# daughter-double3.net
KiCad netlist of a schematic drawn in EAGLE
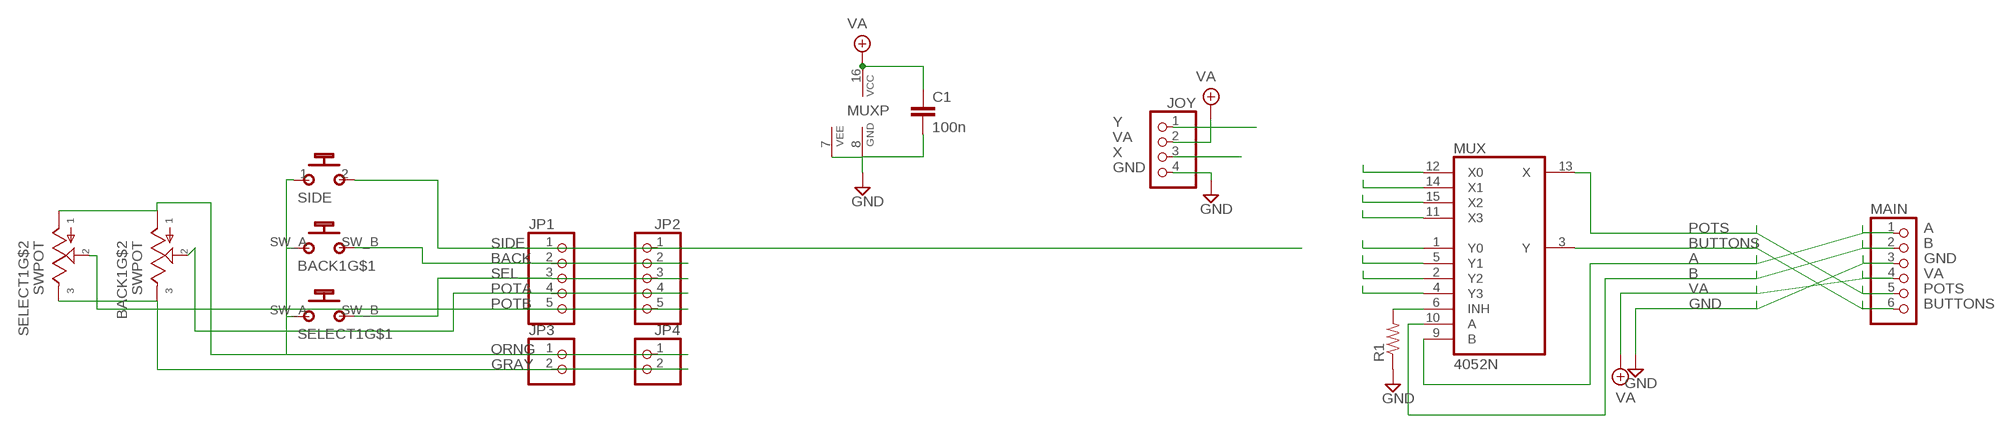
[diagram p0: schematic, sheet 1]

(export (version "E")
  (design (tool "Eeschema 10.0.6"))
  (components
    (comp (ref "BACK1")
      (value "SWPOT")
      (footprint "eagle-import:SWPOT")
      (libsource (lib "eagle-import") (part "SWPOT"))
    )
    (comp (ref "C1")
      (value "100n")
      (footprint "eagle-import:050X030_050_3")
      (libsource (lib "eagle-import") (part "050X030_050"))
    )
    (comp (ref "JOY")
      (value "PINHD-1X4")
      (footprint "eagle-import:1X04")
      (libsource (lib "eagle-import") (part "PINHD-1X4"))
    )
    (comp (ref "JP1")
      (value "PINHD-1X5")
      (footprint "eagle-import:1X05")
      (libsource (lib "eagle-import") (part "PINHD-1X5"))
    )
    (comp (ref "JP2")
      (value "PINHD-1X5")
      (footprint "eagle-import:1X05")
      (libsource (lib "eagle-import") (part "PINHD-1X5"))
    )
    (comp (ref "JP3")
      (value "PINHD-1X2")
      (footprint "eagle-import:1X02")
      (libsource (lib "eagle-import") (part "PINHD-1X2"))
    )
    (comp (ref "JP4")
      (value "PINHD-1X2")
      (footprint "eagle-import:1X02")
      (libsource (lib "eagle-import") (part "PINHD-1X2"))
    )
    (comp (ref "MAIN")
      (value "PINHD-1X6")
      (footprint "eagle-import:1X06")
      (libsource (lib "eagle-import") (part "PINHD-1X6"))
    )
    (comp (ref "MUX")
      (value "4052N")
      (footprint "eagle-import:DIL16")
      (libsource (lib "eagle-import") (part "4052N"))
    )
    (comp (ref "R1")
      (value "6MM.1")
      (footprint "eagle-import:R0207_1V")
      (libsource (lib "eagle-import") (part "6MM.1"))
    )
    (comp (ref "SELECT1")
      (value "SWPOT")
      (footprint "eagle-import:SWPOT")
      (libsource (lib "eagle-import") (part "SWPOT"))
    )
    (comp (ref "SIDE")
      (value "MOMENTARYSPST1")
      (footprint "eagle-import:SPST")
      (libsource (lib "eagle-import") (part "MOMENTARYSPST1"))
    )
  )
  (nets
    (net (code "1") (name "/A") (class "Default")
      (node (ref "MAIN") (pin "1") (pinfunction "1_1") (pintype "passive"))
      (node (ref "MUX") (pin "9") (pinfunction "B_9") (pintype "input"))
    )
    (net (code "2") (name "/B") (class "Default")
      (node (ref "MAIN") (pin "2") (pinfunction "2_2") (pintype "passive"))
      (node (ref "MUX") (pin "10") (pinfunction "A_10") (pintype "input"))
    )
    (net (code "3") (name "/BACK") (class "Default")
      (node (ref "BACK1") (pin "SW_B") (pinfunction "B_B_SW_B") (pintype "passive"))
      (node (ref "JP1") (pin "2") (pinfunction "2_2") (pintype "passive"))
      (node (ref "JP2") (pin "2") (pinfunction "2_2") (pintype "passive"))
    )
    (net (code "4") (name "/BUTTONS") (class "Default")
      (node (ref "MAIN") (pin "6") (pinfunction "6_6") (pintype "passive"))
      (node (ref "MUX") (pin "3") (pinfunction "Y_3") (pintype "bidirectional"))
    )
    (net (code "5") (name "/GRAY") (class "Default")
      (node (ref "BACK1") (pin "POT_A") (pinfunction "POT_A_POT_A") (pintype "passive"))
      (node (ref "JP3") (pin "2") (pinfunction "2_2") (pintype "passive"))
      (node (ref "JP4") (pin "2") (pinfunction "2_2") (pintype "passive"))
      (node (ref "SELECT1") (pin "POT_A") (pinfunction "POT_A_POT_A") (pintype "passive"))
    )
    (net (code "6") (name "/ORNG") (class "Default")
      (node (ref "BACK1") (pin "POT_B") (pinfunction "POT_B_POT_B") (pintype "passive"))
      (node (ref "BACK1") (pin "SW_A") (pinfunction "B_A_SW_A") (pintype "passive"))
      (node (ref "JP3") (pin "1") (pinfunction "1_1") (pintype "passive"))
      (node (ref "JP4") (pin "1") (pinfunction "1_1") (pintype "passive"))
      (node (ref "SELECT1") (pin "POT_B") (pinfunction "POT_B_POT_B") (pintype "passive"))
      (node (ref "SELECT1") (pin "SW_A") (pinfunction "B_A_SW_A") (pintype "passive"))
      (node (ref "SIDE") (pin "1") (pinfunction "P_1") (pintype "passive"))
    )
    (net (code "7") (name "/POTA") (class "Default")
      (node (ref "BACK1") (pin "POT_W") (pinfunction "POT_W_POT_W") (pintype "passive"))
      (node (ref "JP1") (pin "4") (pinfunction "4_4") (pintype "passive"))
      (node (ref "JP2") (pin "4") (pinfunction "4_4") (pintype "passive"))
    )
    (net (code "8") (name "/POTB") (class "Default")
      (node (ref "JP1") (pin "5") (pinfunction "5_5") (pintype "passive"))
      (node (ref "JP2") (pin "5") (pinfunction "5_5") (pintype "passive"))
      (node (ref "SELECT1") (pin "POT_W") (pinfunction "POT_W_POT_W") (pintype "passive"))
    )
    (net (code "9") (name "/POTS") (class "Default")
      (node (ref "MAIN") (pin "5") (pinfunction "5_5") (pintype "passive"))
      (node (ref "MUX") (pin "13") (pinfunction "X_13") (pintype "bidirectional"))
    )
    (net (code "10") (name "/SEL") (class "Default")
      (node (ref "JP1") (pin "3") (pinfunction "3_3") (pintype "passive"))
      (node (ref "JP2") (pin "3") (pinfunction "3_3") (pintype "passive"))
      (node (ref "SELECT1") (pin "SW_B") (pinfunction "B_B_SW_B") (pintype "passive"))
    )
    (net (code "11") (name "/SIDE") (class "Default")
      (node (ref "JP2") (pin "1") (pinfunction "1_1") (pintype "passive"))
      (node (ref "SIDE") (pin "2") (pinfunction "S_2") (pintype "passive"))
    )
    (net (code "12") (name "/X") (class "Default")
      (node (ref "JOY") (pin "1") (pinfunction "1_1") (pintype "passive"))
    )
    (net (code "13") (name "/Y") (class "Default")
      (node (ref "JOY") (pin "3") (pinfunction "3_3") (pintype "passive"))
    )
    (net (code "14") (name "GND") (class "Default")
      (node (ref "C1") (pin "2") (pinfunction "2_2") (pintype "passive"))
      (node (ref "JOY") (pin "4") (pinfunction "4_4") (pintype "passive"))
      (node (ref "MAIN") (pin "3") (pinfunction "3_3") (pintype "passive"))
      (node (ref "MUX") (pin "7") (pinfunction "VEE_7") (pintype "power_in"))
      (node (ref "MUX") (pin "8") (pinfunction "GND_8") (pintype "power_in"))
      (node (ref "R1") (pin "1") (pinfunction "1_1") (pintype "passive"))
    )
    (net (code "15") (name "Net-(MUXA-INH)") (class "Default")
      (node (ref "MUX") (pin "6") (pinfunction "INH_6") (pintype "input"))
      (node (ref "R1") (pin "2") (pinfunction "2_2") (pintype "passive"))
    )
    (net (code "16") (name "VA") (class "Default")
      (node (ref "C1") (pin "1") (pinfunction "1_1") (pintype "passive"))
      (node (ref "JOY") (pin "2") (pinfunction "2_2") (pintype "passive"))
      (node (ref "MAIN") (pin "4") (pinfunction "4_4") (pintype "passive"))
      (node (ref "MUX") (pin "16") (pinfunction "VCC_16") (pintype "power_in"))
    )
    (net (code "17") (name "unconnected-(JP1-Pad1)") (class "Default")
      (node (ref "JP1") (pin "1") (pinfunction "1_1") (pintype "passive"))
    )
    (net (code "18") (name "unconnected-(MUXA-X0-Pad12)") (class "Default")
      (node (ref "MUX") (pin "12") (pinfunction "X0_12") (pintype "bidirectional"))
    )
    (net (code "19") (name "unconnected-(MUXA-X1-Pad14)") (class "Default")
      (node (ref "MUX") (pin "14") (pinfunction "X1_14") (pintype "bidirectional"))
    )
    (net (code "20") (name "unconnected-(MUXA-X2-Pad15)") (class "Default")
      (node (ref "MUX") (pin "15") (pinfunction "X2_15") (pintype "bidirectional"))
    )
    (net (code "21") (name "unconnected-(MUXA-X3-Pad11)") (class "Default")
      (node (ref "MUX") (pin "11") (pinfunction "X3_11") (pintype "bidirectional"))
    )
    (net (code "22") (name "unconnected-(MUXA-Y0-Pad1)") (class "Default")
      (node (ref "MUX") (pin "1") (pinfunction "Y0_1") (pintype "bidirectional"))
    )
    (net (code "23") (name "unconnected-(MUXA-Y1-Pad5)") (class "Default")
      (node (ref "MUX") (pin "5") (pinfunction "Y1_5") (pintype "bidirectional"))
    )
    (net (code "24") (name "unconnected-(MUXA-Y2-Pad2)") (class "Default")
      (node (ref "MUX") (pin "2") (pinfunction "Y2_2") (pintype "bidirectional"))
    )
    (net (code "25") (name "unconnected-(MUXA-Y3-Pad4)") (class "Default")
      (node (ref "MUX") (pin "4") (pinfunction "Y3_4") (pintype "bidirectional"))
    )
  )
)
